# Card-Shuffler.net
KiCad netlist of a schematic drawn in Altium Designer
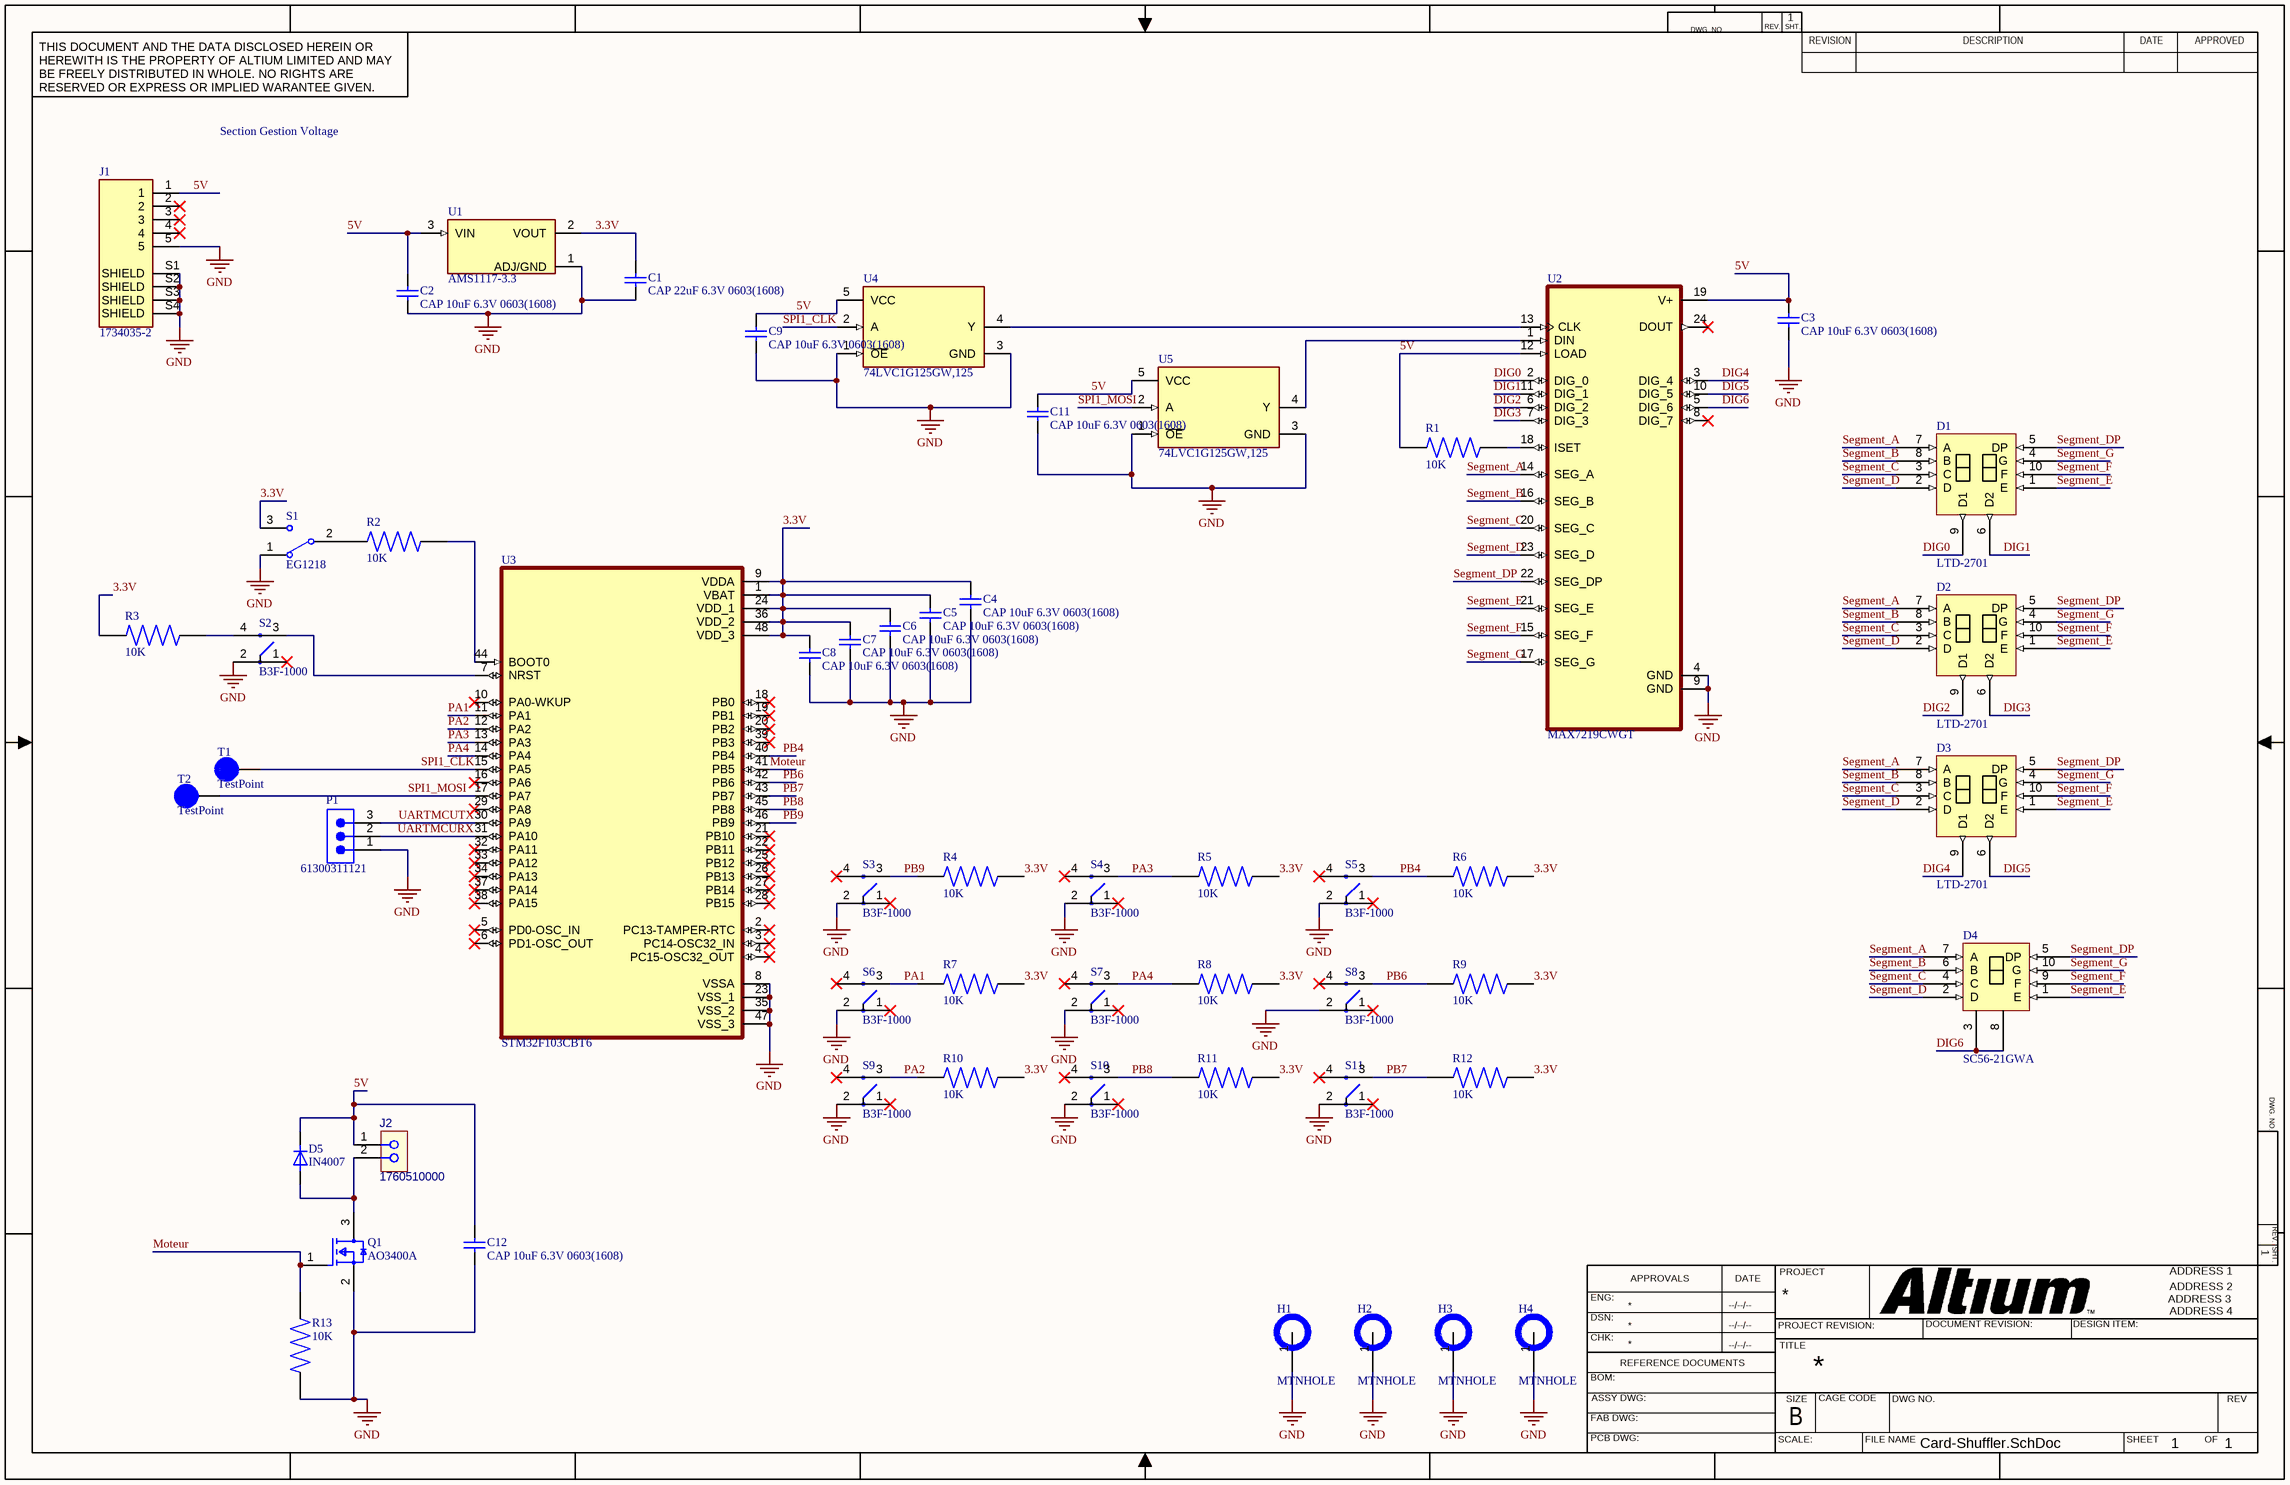
[diagram p0: Card-Shuffler.SchDoc]

(export (version "E")
  (design (tool "Eeschema 10.0.6"))
  (components
    (comp (ref "C1")
      (value "CAP 22uF 6.3V 0603(1608)")
      (footprint "CAPC0603(1608)100_M")
      (description "CAP 22uF 6.3V ±10% 0603 (1608 Metric) Thickness 1mm SMD")
      (fields (field (name "TOLERANCE") "Â±10%"))
      (libsource (lib "Altium Content Vault") (part "CAP"))
    )
    (comp (ref "C2")
      (value "CAP 10uF 6.3V 0603(1608)")
      (footprint "CAPC0603(1608)100_M")
      (description "CAP 10uF 6.3V ±10% 0603 (1608 Metric) Thickness 1mm SMD")
      (fields (field (name "TOLERANCE") "Â±10%"))
      (libsource (lib "Altium Content Vault") (part "CAP"))
    )
    (comp (ref "C3")
      (value "CAP 10uF 6.3V 0603(1608)")
      (footprint "CAPC0603(1608)100_M")
      (description "CAP 10uF 6.3V ±10% 0603 (1608 Metric) Thickness 1mm SMD")
      (fields (field (name "TOLERANCE") "Â±10%"))
      (libsource (lib "Altium Content Vault") (part "CAP"))
    )
    (comp (ref "C4")
      (value "CAP 10uF 6.3V 0603(1608)")
      (footprint "CAPC0603(1608)100_M")
      (description "CAP 10uF 6.3V ±10% 0603 (1608 Metric) Thickness 1mm SMD")
      (fields (field (name "TOLERANCE") "Â±10%"))
      (libsource (lib "Altium Content Vault") (part "CAP"))
    )
    (comp (ref "C5")
      (value "CAP 10uF 6.3V 0603(1608)")
      (footprint "CAPC0603(1608)100_M")
      (description "CAP 10uF 6.3V ±10% 0603 (1608 Metric) Thickness 1mm SMD")
      (fields (field (name "TOLERANCE") "Â±10%"))
      (libsource (lib "Altium Content Vault") (part "CAP"))
    )
    (comp (ref "C6")
      (value "CAP 10uF 6.3V 0603(1608)")
      (footprint "CAPC0603(1608)100_M")
      (description "CAP 10uF 6.3V ±10% 0603 (1608 Metric) Thickness 1mm SMD")
      (fields (field (name "TOLERANCE") "Â±10%"))
      (libsource (lib "Altium Content Vault") (part "CAP"))
    )
    (comp (ref "C7")
      (value "CAP 10uF 6.3V 0603(1608)")
      (footprint "CAPC0603(1608)100_M")
      (description "CAP 10uF 6.3V ±10% 0603 (1608 Metric) Thickness 1mm SMD")
      (fields (field (name "TOLERANCE") "Â±10%"))
      (libsource (lib "Altium Content Vault") (part "CAP"))
    )
    (comp (ref "C8")
      (value "CAP 10uF 6.3V 0603(1608)")
      (footprint "CAPC0603(1608)100_M")
      (description "CAP 10uF 6.3V ±10% 0603 (1608 Metric) Thickness 1mm SMD")
      (fields (field (name "TOLERANCE") "Â±10%"))
      (libsource (lib "Altium Content Vault") (part "CAP"))
    )
    (comp (ref "C9")
      (value "CAP 10uF 6.3V 0603(1608)")
      (footprint "CAPC0603(1608)100_M")
      (description "CAP 10uF 6.3V ±10% 0603 (1608 Metric) Thickness 1mm SMD")
      (fields (field (name "TOLERANCE") "Â±10%"))
      (libsource (lib "Altium Content Vault") (part "CAP"))
    )
    (comp (ref "C11")
      (value "CAP 10uF 6.3V 0603(1608)")
      (footprint "CAPC0603(1608)100_M")
      (description "CAP 10uF 6.3V ±10% 0603 (1608 Metric) Thickness 1mm SMD")
      (fields (field (name "TOLERANCE") "Â±10%"))
      (libsource (lib "Altium Content Vault") (part "CAP"))
    )
    (comp (ref "C12")
      (value "CAP 10uF 6.3V 0603(1608)")
      (footprint "CAPC0603(1608)100_M")
      (description "CAP 10uF 6.3V ±10% 0603 (1608 Metric) Thickness 1mm SMD")
      (fields (field (name "TOLERANCE") "Â±10%"))
      (libsource (lib "Altium Content Vault") (part "CAP"))
    )
    (comp (ref "D1")
      (value "LTD-2701")
      (footprint "LTD-701JD")
      (description "Afficheur 7-segments double")
      (libsource (lib "Pieces") (part "LTD-2701"))
    )
    (comp (ref "D2")
      (value "LTD-2701")
      (footprint "LTD-701JD")
      (description "Afficheur 7-segments double")
      (libsource (lib "Pieces") (part "LTD-2701"))
    )
    (comp (ref "D3")
      (value "LTD-2701")
      (footprint "LTD-701JD")
      (description "Afficheur 7-segments double")
      (libsource (lib "Pieces") (part "LTD-2701"))
    )
    (comp (ref "D4")
      (value "SC56-21GWA")
      (footprint "SC56-21GWA")
      (description "Afficheur 7-Segment")
      (libsource (lib "Pieces") (part "SC56-21GWA"))
    )
    (comp (ref "D5")
      (value "IN4007")
      (footprint "DIOAD1070W78L470D235P")
      (description "Diode Standard 1000 V 1A Through Hole DO-204AL (DO-41)")
      (fields (field (name "MF") "Vishay Semiconductor"))
      (libsource (lib "Pieces") (part "IN4007"))
    )
    (comp (ref "H1") (value "MTNHOLE") (footprint "MTHOLE1_LAB4") (libsource (lib "Pieces") (part "MTNHOLE")))
    (comp (ref "H2") (value "MTNHOLE") (footprint "MTHOLE1_LAB4") (libsource (lib "Pieces") (part "MTNHOLE")))
    (comp (ref "H3") (value "MTNHOLE") (footprint "MTHOLE1_LAB4") (libsource (lib "Pieces") (part "MTNHOLE")))
    (comp (ref "H4") (value "MTNHOLE") (footprint "MTHOLE1_LAB4") (libsource (lib "Pieces") (part "MTNHOLE")))
    (comp (ref "J1")
      (value "1734035-2")
      (footprint "CONN_1734035-2")
      (description "CONNECTOR, RECEPTACLE, MINI-USB, 1 PORT, SERIES B, RIGHT ANGLE ¦ TE Connectivity 1734035-2")
      (fields (field (name "MF") "TE Connectivity"))
      (libsource (lib "Pieces") (part "1734035-2"))
    )
    (comp (ref "J2")
      (value "1760510000")
      (footprint "CONN_TERM_BLOCK_2POS_5mm_Model1")
      (description "CONN TERM BLOCK 2POS 5mm pitch")
      (libsource (lib "Pieces") (part "CONN_TERM_BLOCK_2POS_5mm_MODEL2"))
    )
    (comp (ref "P1")
      (value "61300311121")
      (footprint "CONN_HDR_3POS_100MILS_TH")
      (description "Header 3pins single row, TH")
      (libsource (lib "Pieces") (part "CONN_HEADER_3POS"))
    )
    (comp (ref "Q1")
      (value "AO3400A")
      (footprint "FP-SOT23-MFG")
      (description "MOSFET N-CH 30V 5.7A SOT23")
      (libsource (lib "Altium Content Vault") (part "0a9ea7c96deaaede766a5b531c28de0"))
    )
    (comp (ref "R1")
      (value "10K")
      (footprint "RES_ERJU03F1503V")
      (description "0201 anti-sulfurated resistor 0603 Anti-Sulfurated")
      (fields (field (name "MF") "Panasonic") (field (name "MP") "ERJ-U03F1503V"))
      (libsource (lib "Pieces") (part "ERJU03F1503V"))
    )
    (comp (ref "R2")
      (value "10K")
      (footprint "RES_ERJU03F1503V")
      (description "0201 anti-sulfurated resistor 0603 Anti-Sulfurated")
      (fields (field (name "MF") "Panasonic") (field (name "MP") "ERJ-U03F1503V"))
      (libsource (lib "Pieces") (part "ERJU03F1503V"))
    )
    (comp (ref "R3")
      (value "10K")
      (footprint "RES_ERJU03F1503V")
      (description "0201 anti-sulfurated resistor 0603 Anti-Sulfurated")
      (fields (field (name "MF") "Panasonic") (field (name "MP") "ERJ-U03F1503V"))
      (libsource (lib "Pieces") (part "ERJU03F1503V"))
    )
    (comp (ref "R4")
      (value "10K")
      (footprint "RES_ERJU03F1503V")
      (description "0201 anti-sulfurated resistor 0603 Anti-Sulfurated")
      (fields (field (name "MF") "Panasonic") (field (name "MP") "ERJ-U03F1503V"))
      (libsource (lib "Pieces") (part "ERJU03F1503V"))
    )
    (comp (ref "R5")
      (value "10K")
      (footprint "RES_ERJU03F1503V")
      (description "0201 anti-sulfurated resistor 0603 Anti-Sulfurated")
      (fields (field (name "MF") "Panasonic") (field (name "MP") "ERJ-U03F1503V"))
      (libsource (lib "Pieces") (part "ERJU03F1503V"))
    )
    (comp (ref "R6")
      (value "10K")
      (footprint "RES_ERJU03F1503V")
      (description "0201 anti-sulfurated resistor 0603 Anti-Sulfurated")
      (fields (field (name "MF") "Panasonic") (field (name "MP") "ERJ-U03F1503V"))
      (libsource (lib "Pieces") (part "ERJU03F1503V"))
    )
    (comp (ref "R7")
      (value "10K")
      (footprint "RES_ERJU03F1503V")
      (description "0201 anti-sulfurated resistor 0603 Anti-Sulfurated")
      (fields (field (name "MF") "Panasonic") (field (name "MP") "ERJ-U03F1503V"))
      (libsource (lib "Pieces") (part "ERJU03F1503V"))
    )
    (comp (ref "R8")
      (value "10K")
      (footprint "RES_ERJU03F1503V")
      (description "0201 anti-sulfurated resistor 0603 Anti-Sulfurated")
      (fields (field (name "MF") "Panasonic") (field (name "MP") "ERJ-U03F1503V"))
      (libsource (lib "Pieces") (part "ERJU03F1503V"))
    )
    (comp (ref "R9")
      (value "10K")
      (footprint "RES_ERJU03F1503V")
      (description "0201 anti-sulfurated resistor 0603 Anti-Sulfurated")
      (fields (field (name "MF") "Panasonic") (field (name "MP") "ERJ-U03F1503V"))
      (libsource (lib "Pieces") (part "ERJU03F1503V"))
    )
    (comp (ref "R10")
      (value "10K")
      (footprint "RES_ERJU03F1503V")
      (description "0201 anti-sulfurated resistor 0603 Anti-Sulfurated")
      (fields (field (name "MF") "Panasonic") (field (name "MP") "ERJ-U03F1503V"))
      (libsource (lib "Pieces") (part "ERJU03F1503V"))
    )
    (comp (ref "R11")
      (value "10K")
      (footprint "RES_ERJU03F1503V")
      (description "0201 anti-sulfurated resistor 0603 Anti-Sulfurated")
      (fields (field (name "MF") "Panasonic") (field (name "MP") "ERJ-U03F1503V"))
      (libsource (lib "Pieces") (part "ERJU03F1503V"))
    )
    (comp (ref "R12")
      (value "10K")
      (footprint "RES_ERJU03F1503V")
      (description "0201 anti-sulfurated resistor 0603 Anti-Sulfurated")
      (fields (field (name "MF") "Panasonic") (field (name "MP") "ERJ-U03F1503V"))
      (libsource (lib "Pieces") (part "ERJU03F1503V"))
    )
    (comp (ref "R13")
      (value "10K")
      (footprint "RES_ERJU03F1503V")
      (description "0201 anti-sulfurated resistor 0603 Anti-Sulfurated")
      (fields (field (name "MF") "Panasonic") (field (name "MP") "ERJ-U03F1503V"))
      (libsource (lib "Pieces") (part "ERJU03F1503V"))
    )
    (comp (ref "S1")
      (value "EG1218")
      (footprint "ESWI-EG1218_V")
      (description "Slide Switch, 500 V, -20 to 70 degC, 3-Pin THD, RoHS")
      (libsource (lib "Altium Content Vault") (part "SW-SPDT-3_B"))
    )
    (comp (ref "S2")
      (value "B3F-1000")
      (footprint "SW_B3F-1000")
      (description "Switch Tactile N.O. SPST Flat Round Button PC Pins 0.05A 24VDC 1000000Cycles 0.98N Thru-Hole Bag")
      (fields (field (name "MF") "Omron") (field (name "MP") "B3F1000"))
      (libsource (lib "Pieces") (part "B3F-1000"))
    )
    (comp (ref "S3")
      (value "B3F-1000")
      (footprint "SW_B3F-1000")
      (description "Switch Tactile N.O. SPST Flat Round Button PC Pins 0.05A 24VDC 1000000Cycles 0.98N Thru-Hole Bag")
      (fields (field (name "MF") "Omron") (field (name "MP") "B3F1000"))
      (libsource (lib "Pieces") (part "B3F-1000"))
    )
    (comp (ref "S4")
      (value "B3F-1000")
      (footprint "SW_B3F-1000")
      (description "Switch Tactile N.O. SPST Flat Round Button PC Pins 0.05A 24VDC 1000000Cycles 0.98N Thru-Hole Bag")
      (fields (field (name "MF") "Omron") (field (name "MP") "B3F1000"))
      (libsource (lib "Pieces") (part "B3F-1000"))
    )
    (comp (ref "S5")
      (value "B3F-1000")
      (footprint "SW_B3F-1000")
      (description "Switch Tactile N.O. SPST Flat Round Button PC Pins 0.05A 24VDC 1000000Cycles 0.98N Thru-Hole Bag")
      (fields (field (name "MF") "Omron") (field (name "MP") "B3F1000"))
      (libsource (lib "Pieces") (part "B3F-1000"))
    )
    (comp (ref "S6")
      (value "B3F-1000")
      (footprint "SW_B3F-1000")
      (description "Switch Tactile N.O. SPST Flat Round Button PC Pins 0.05A 24VDC 1000000Cycles 0.98N Thru-Hole Bag")
      (fields (field (name "MF") "Omron") (field (name "MP") "B3F1000"))
      (libsource (lib "Pieces") (part "B3F-1000"))
    )
    (comp (ref "S7")
      (value "B3F-1000")
      (footprint "SW_B3F-1000")
      (description "Switch Tactile N.O. SPST Flat Round Button PC Pins 0.05A 24VDC 1000000Cycles 0.98N Thru-Hole Bag")
      (fields (field (name "MF") "Omron") (field (name "MP") "B3F1000"))
      (libsource (lib "Pieces") (part "B3F-1000"))
    )
    (comp (ref "S8")
      (value "B3F-1000")
      (footprint "SW_B3F-1000")
      (description "Switch Tactile N.O. SPST Flat Round Button PC Pins 0.05A 24VDC 1000000Cycles 0.98N Thru-Hole Bag")
      (fields (field (name "MF") "Omron") (field (name "MP") "B3F1000"))
      (libsource (lib "Pieces") (part "B3F-1000"))
    )
    (comp (ref "S9")
      (value "B3F-1000")
      (footprint "SW_B3F-1000")
      (description "Switch Tactile N.O. SPST Flat Round Button PC Pins 0.05A 24VDC 1000000Cycles 0.98N Thru-Hole Bag")
      (fields (field (name "MF") "Omron") (field (name "MP") "B3F1000"))
      (libsource (lib "Pieces") (part "B3F-1000"))
    )
    (comp (ref "S10")
      (value "B3F-1000")
      (footprint "SW_B3F-1000")
      (description "Switch Tactile N.O. SPST Flat Round Button PC Pins 0.05A 24VDC 1000000Cycles 0.98N Thru-Hole Bag")
      (fields (field (name "MF") "Omron") (field (name "MP") "B3F1000"))
      (libsource (lib "Pieces") (part "B3F-1000"))
    )
    (comp (ref "S11")
      (value "B3F-1000")
      (footprint "SW_B3F-1000")
      (description "Switch Tactile N.O. SPST Flat Round Button PC Pins 0.05A 24VDC 1000000Cycles 0.98N Thru-Hole Bag")
      (fields (field (name "MF") "Omron") (field (name "MP") "B3F1000"))
      (libsource (lib "Pieces") (part "B3F-1000"))
    )
    (comp (ref "T1")
      (value "TestPoint")
      (footprint "Testpoint")
      (libsource (lib "Pieces") (part "TestPoint"))
    )
    (comp (ref "T2")
      (value "TestPoint")
      (footprint "Testpoint")
      (libsource (lib "Pieces") (part "TestPoint"))
    )
    (comp (ref "U1")
      (value "AMS1117-3.3")
      (footprint "SOT229P700X180-4N")
      (description "Linear Voltage Regulator IC Positive Fixed 1 Output 1A SOT-223-3L")
      (fields (field (name "MF") "UMW"))
      (libsource (lib "Pieces") (part "AMS1117-3.3"))
    )
    (comp (ref "U2")
      (value "MAX7219CWGT")
      (footprint "SOIC127P1032X265-24N")
      (description "IC DRVR 7 SEGMNT 8 DIGIT 24SOIC")
      (fields (field (name "MF") "Analog Devices") (field (name "MP") "MAX7219CWG+"))
      (libsource (lib "Pieces") (part "MAX7219CWGT"))
    )
    (comp (ref "U3")
      (value "STM32F103CBT6")
      (footprint "QFP50P900X900X160-48N")
      (description "ARMÂ® CortexÂ®-M3 STM32F1 Microcontroller IC 32-Bit Single-Core 72MHz 128KB (128K x 8) FLASH")
      (fields (field (name "MF") "STMicroelectronics"))
      (libsource (lib "Pieces") (part "STM32F103CBT6"))
    )
    (comp (ref "U4")
      (value "74LVC1G125GW,125")
      (footprint "FP-SOT353-1-IPC_A")
      (description "IC BUF NON-INVERT 5.5V 5TSSOP")
      (libsource (lib "Altium Content Vault") (part "ce4f934f0121cbd2948622023bc44d6"))
    )
    (comp (ref "U5")
      (value "74LVC1G125GW,125")
      (footprint "FP-SOT353-1-IPC_A")
      (description "IC BUF NON-INVERT 5.5V 5TSSOP")
      (libsource (lib "Altium Content Vault") (part "ce4f934f0121cbd2948622023bc44d6"))
    )
  )
  (nets
    (net (code "1") (name "/3.3V") (class "Default")
      (node (ref "C1") (pin "2") (pinfunction "2_2") (pintype "passive"))
      (node (ref "C4") (pin "2") (pinfunction "2_2") (pintype "passive"))
      (node (ref "C5") (pin "2") (pinfunction "2_2") (pintype "passive"))
      (node (ref "C6") (pin "2") (pinfunction "2_2") (pintype "passive"))
      (node (ref "C7") (pin "2") (pinfunction "2_2") (pintype "passive"))
      (node (ref "C8") (pin "2") (pinfunction "2_2") (pintype "passive"))
      (node (ref "R10") (pin "2") (pinfunction "2_2") (pintype "passive"))
      (node (ref "R11") (pin "2") (pinfunction "2_2") (pintype "passive"))
      (node (ref "R12") (pin "2") (pinfunction "2_2") (pintype "passive"))
      (node (ref "R3") (pin "1") (pinfunction "1_1") (pintype "passive"))
      (node (ref "R4") (pin "2") (pinfunction "2_2") (pintype "passive"))
      (node (ref "R5") (pin "2") (pinfunction "2_2") (pintype "passive"))
      (node (ref "R6") (pin "2") (pinfunction "2_2") (pintype "passive"))
      (node (ref "R7") (pin "2") (pinfunction "2_2") (pintype "passive"))
      (node (ref "R8") (pin "2") (pinfunction "2_2") (pintype "passive"))
      (node (ref "R9") (pin "2") (pinfunction "2_2") (pintype "passive"))
      (node (ref "S1") (pin "3") (pinfunction "3_3") (pintype "passive"))
      (node (ref "U1") (pin "2") (pinfunction "VOUT_2") (pintype "passive"))
      (node (ref "U3") (pin "1") (pinfunction "VBAT_1") (pintype "power_in"))
      (node (ref "U3") (pin "24") (pinfunction "VDD_1_24") (pintype "power_in"))
      (node (ref "U3") (pin "36") (pinfunction "VDD_2_36") (pintype "power_in"))
      (node (ref "U3") (pin "48") (pinfunction "VDD_3_48") (pintype "power_in"))
      (node (ref "U3") (pin "9") (pinfunction "VDDA_9") (pintype "power_in"))
    )
    (net (code "2") (name "/5V") (class "Default")
      (node (ref "C11") (pin "2") (pinfunction "2_2") (pintype "passive"))
      (node (ref "C12") (pin "2") (pinfunction "2_2") (pintype "passive"))
      (node (ref "C2") (pin "2") (pinfunction "2_2") (pintype "passive"))
      (node (ref "C3") (pin "2") (pinfunction "2_2") (pintype "passive"))
      (node (ref "C9") (pin "1") (pinfunction "1_1") (pintype "passive"))
      (node (ref "D5") (pin "C") (pinfunction "C_C") (pintype "passive"))
      (node (ref "J1") (pin "1") (pinfunction "1_1") (pintype "passive"))
      (node (ref "J2") (pin "1") (pinfunction "1_1") (pintype "passive"))
      (node (ref "R1") (pin "1") (pinfunction "1_1") (pintype "passive"))
      (node (ref "U1") (pin "3") (pinfunction "VIN_3") (pintype "input"))
      (node (ref "U2") (pin "12") (pinfunction "LOAD_12") (pintype "input"))
      (node (ref "U2") (pin "19") (pinfunction "V+_19") (pintype "power_in"))
      (node (ref "U4") (pin "5") (pinfunction "VCC_5") (pintype "power_in"))
      (node (ref "U5") (pin "5") (pinfunction "VCC_5") (pintype "power_in"))
    )
    (net (code "3") (name "/DIG0") (class "Default")
      (node (ref "D1") (pin "9") (pinfunction "D1_9") (pintype "output"))
      (node (ref "U2") (pin "2") (pinfunction "DIG_0_2") (pintype "bidirectional"))
    )
    (net (code "4") (name "/DIG1") (class "Default")
      (node (ref "D1") (pin "6") (pinfunction "D2_6") (pintype "output"))
      (node (ref "U2") (pin "11") (pinfunction "DIG_1_11") (pintype "bidirectional"))
    )
    (net (code "5") (name "/DIG2") (class "Default")
      (node (ref "D2") (pin "9") (pinfunction "D1_9") (pintype "output"))
      (node (ref "U2") (pin "6") (pinfunction "DIG_2_6") (pintype "bidirectional"))
    )
    (net (code "6") (name "/DIG3") (class "Default")
      (node (ref "D2") (pin "6") (pinfunction "D2_6") (pintype "output"))
      (node (ref "U2") (pin "7") (pinfunction "DIG_3_7") (pintype "bidirectional"))
    )
    (net (code "7") (name "/DIG4") (class "Default")
      (node (ref "D3") (pin "9") (pinfunction "D1_9") (pintype "output"))
      (node (ref "U2") (pin "3") (pinfunction "DIG_4_3") (pintype "bidirectional"))
    )
    (net (code "8") (name "/DIG5") (class "Default")
      (node (ref "D3") (pin "6") (pinfunction "D2_6") (pintype "output"))
      (node (ref "U2") (pin "10") (pinfunction "DIG_5_10") (pintype "bidirectional"))
    )
    (net (code "9") (name "/DIG6") (class "Default")
      (node (ref "D4") (pin "3") (pintype "power_in"))
      (node (ref "D4") (pin "8") (pintype "power_in"))
      (node (ref "U2") (pin "5") (pinfunction "DIG_6_5") (pintype "bidirectional"))
    )
    (net (code "10") (name "/Moteur") (class "Default")
      (node (ref "Q1") (pin "1") (pinfunction "G_1") (pintype "passive"))
      (node (ref "R13") (pin "2") (pinfunction "2_2") (pintype "passive"))
      (node (ref "U3") (pin "41") (pinfunction "PB5_41") (pintype "bidirectional"))
    )
    (net (code "11") (name "/PA1") (class "Default")
      (node (ref "R7") (pin "1") (pinfunction "1_1") (pintype "passive"))
      (node (ref "S6") (pin "3") (pinfunction "3_3") (pintype "passive"))
      (node (ref "U3") (pin "11") (pinfunction "PA1_11") (pintype "bidirectional"))
    )
    (net (code "12") (name "/PA2") (class "Default")
      (node (ref "R10") (pin "1") (pinfunction "1_1") (pintype "passive"))
      (node (ref "S9") (pin "3") (pinfunction "3_3") (pintype "passive"))
      (node (ref "U3") (pin "12") (pinfunction "PA2_12") (pintype "bidirectional"))
    )
    (net (code "13") (name "/PA3") (class "Default")
      (node (ref "R5") (pin "1") (pinfunction "1_1") (pintype "passive"))
      (node (ref "S4") (pin "3") (pinfunction "3_3") (pintype "passive"))
      (node (ref "U3") (pin "13") (pinfunction "PA3_13") (pintype "bidirectional"))
    )
    (net (code "14") (name "/PA4") (class "Default")
      (node (ref "R8") (pin "1") (pinfunction "1_1") (pintype "passive"))
      (node (ref "S7") (pin "3") (pinfunction "3_3") (pintype "passive"))
      (node (ref "U3") (pin "14") (pinfunction "PA4_14") (pintype "bidirectional"))
    )
    (net (code "15") (name "/PB4") (class "Default")
      (node (ref "R6") (pin "1") (pinfunction "1_1") (pintype "passive"))
      (node (ref "S5") (pin "3") (pinfunction "3_3") (pintype "passive"))
      (node (ref "U3") (pin "40") (pinfunction "PB4_40") (pintype "bidirectional"))
    )
    (net (code "16") (name "/PB6") (class "Default")
      (node (ref "R9") (pin "1") (pinfunction "1_1") (pintype "passive"))
      (node (ref "S8") (pin "3") (pinfunction "3_3") (pintype "passive"))
      (node (ref "U3") (pin "42") (pinfunction "PB6_42") (pintype "bidirectional"))
    )
    (net (code "17") (name "/PB7") (class "Default")
      (node (ref "R12") (pin "1") (pinfunction "1_1") (pintype "passive"))
      (node (ref "S11") (pin "3") (pinfunction "3_3") (pintype "passive"))
      (node (ref "U3") (pin "43") (pinfunction "PB7_43") (pintype "bidirectional"))
    )
    (net (code "18") (name "/PB8") (class "Default")
      (node (ref "R11") (pin "1") (pinfunction "1_1") (pintype "passive"))
      (node (ref "S10") (pin "3") (pinfunction "3_3") (pintype "passive"))
      (node (ref "U3") (pin "45") (pinfunction "PB8_45") (pintype "bidirectional"))
    )
    (net (code "19") (name "/PB9") (class "Default")
      (node (ref "R4") (pin "1") (pinfunction "1_1") (pintype "passive"))
      (node (ref "S3") (pin "3") (pinfunction "3_3") (pintype "passive"))
      (node (ref "U3") (pin "46") (pinfunction "PB9_46") (pintype "bidirectional"))
    )
    (net (code "20") (name "/SPI1_CLK") (class "Default")
      (node (ref "T1") (pin "1") (pinfunction "1_1") (pintype "passive"))
      (node (ref "U3") (pin "15") (pinfunction "PA5_15") (pintype "bidirectional"))
      (node (ref "U4") (pin "2") (pinfunction "A_2") (pintype "input"))
    )
    (net (code "21") (name "/SPI1_MOSI") (class "Default")
      (node (ref "T2") (pin "1") (pinfunction "1_1") (pintype "passive"))
      (node (ref "U3") (pin "17") (pinfunction "PA7_17") (pintype "bidirectional"))
      (node (ref "U5") (pin "2") (pinfunction "A_2") (pintype "input"))
    )
    (net (code "22") (name "/Segment_A") (class "Default")
      (node (ref "D1") (pin "7") (pinfunction "A_7") (pintype "input"))
      (node (ref "D2") (pin "7") (pinfunction "A_7") (pintype "input"))
      (node (ref "D3") (pin "7") (pinfunction "A_7") (pintype "input"))
      (node (ref "D4") (pin "7") (pinfunction "A_7") (pintype "input"))
      (node (ref "U2") (pin "14") (pinfunction "SEG_A_14") (pintype "bidirectional"))
    )
    (net (code "23") (name "/Segment_B") (class "Default")
      (node (ref "D1") (pin "8") (pinfunction "B_8") (pintype "input"))
      (node (ref "D2") (pin "8") (pinfunction "B_8") (pintype "input"))
      (node (ref "D3") (pin "8") (pinfunction "B_8") (pintype "input"))
      (node (ref "D4") (pin "6") (pinfunction "B_6") (pintype "input"))
      (node (ref "U2") (pin "16") (pinfunction "SEG_B_16") (pintype "bidirectional"))
    )
    (net (code "24") (name "/Segment_C") (class "Default")
      (node (ref "D1") (pin "3") (pinfunction "C_3") (pintype "input"))
      (node (ref "D2") (pin "3") (pinfunction "C_3") (pintype "input"))
      (node (ref "D3") (pin "3") (pinfunction "C_3") (pintype "input"))
      (node (ref "D4") (pin "4") (pinfunction "C_4") (pintype "input"))
      (node (ref "U2") (pin "20") (pinfunction "SEG_C_20") (pintype "bidirectional"))
    )
    (net (code "25") (name "/Segment_D") (class "Default")
      (node (ref "D1") (pin "2") (pinfunction "D_2") (pintype "input"))
      (node (ref "D2") (pin "2") (pinfunction "D_2") (pintype "input"))
      (node (ref "D3") (pin "2") (pinfunction "D_2") (pintype "input"))
      (node (ref "D4") (pin "2") (pinfunction "D_2") (pintype "input"))
      (node (ref "U2") (pin "23") (pinfunction "SEG_D_23") (pintype "bidirectional"))
    )
    (net (code "26") (name "/Segment_DP") (class "Default")
      (node (ref "D1") (pin "5") (pinfunction "DP_5") (pintype "input"))
      (node (ref "D2") (pin "5") (pinfunction "DP_5") (pintype "input"))
      (node (ref "D3") (pin "5") (pinfunction "DP_5") (pintype "input"))
      (node (ref "D4") (pin "5") (pinfunction "DP_5") (pintype "input"))
      (node (ref "U2") (pin "22") (pinfunction "SEG_DP_22") (pintype "bidirectional"))
    )
    (net (code "27") (name "/Segment_E") (class "Default")
      (node (ref "D1") (pin "1") (pinfunction "E_1") (pintype "input"))
      (node (ref "D2") (pin "1") (pinfunction "E_1") (pintype "input"))
      (node (ref "D3") (pin "1") (pinfunction "E_1") (pintype "input"))
      (node (ref "D4") (pin "1") (pinfunction "E_1") (pintype "input"))
      (node (ref "U2") (pin "21") (pinfunction "SEG_E_21") (pintype "bidirectional"))
    )
    (net (code "28") (name "/Segment_F") (class "Default")
      (node (ref "D1") (pin "10") (pinfunction "F_10") (pintype "input"))
      (node (ref "D2") (pin "10") (pinfunction "F_10") (pintype "input"))
      (node (ref "D3") (pin "10") (pinfunction "F_10") (pintype "input"))
      (node (ref "D4") (pin "9") (pinfunction "F_9") (pintype "input"))
      (node (ref "U2") (pin "15") (pinfunction "SEG_F_15") (pintype "bidirectional"))
    )
    (net (code "29") (name "/Segment_G") (class "Default")
      (node (ref "D1") (pin "4") (pinfunction "G_4") (pintype "input"))
      (node (ref "D2") (pin "4") (pinfunction "G_4") (pintype "input"))
      (node (ref "D3") (pin "4") (pinfunction "G_4") (pintype "input"))
      (node (ref "D4") (pin "10") (pinfunction "G_10") (pintype "input"))
      (node (ref "U2") (pin "17") (pinfunction "SEG_G_17") (pintype "bidirectional"))
    )
    (net (code "30") (name "/UARTMCURX") (class "Default")
      (node (ref "P1") (pin "2") (pinfunction "2_2") (pintype "passive"))
      (node (ref "U3") (pin "31") (pinfunction "PA10_31") (pintype "bidirectional"))
    )
    (net (code "31") (name "/UARTMCUTX") (class "Default")
      (node (ref "P1") (pin "3") (pinfunction "3_3") (pintype "passive"))
      (node (ref "U3") (pin "30") (pinfunction "PA9_30") (pintype "bidirectional"))
    )
    (net (code "32") (name "GND") (class "Default")
      (node (ref "C1") (pin "1") (pinfunction "1_1") (pintype "passive"))
      (node (ref "C11") (pin "1") (pinfunction "1_1") (pintype "passive"))
      (node (ref "C12") (pin "1") (pinfunction "1_1") (pintype "passive"))
      (node (ref "C2") (pin "1") (pinfunction "1_1") (pintype "passive"))
      (node (ref "C3") (pin "1") (pinfunction "1_1") (pintype "passive"))
      (node (ref "C4") (pin "1") (pinfunction "1_1") (pintype "passive"))
      (node (ref "C5") (pin "1") (pinfunction "1_1") (pintype "passive"))
      (node (ref "C6") (pin "1") (pinfunction "1_1") (pintype "passive"))
      (node (ref "C7") (pin "1") (pinfunction "1_1") (pintype "passive"))
      (node (ref "C8") (pin "1") (pinfunction "1_1") (pintype "passive"))
      (node (ref "C9") (pin "2") (pinfunction "2_2") (pintype "passive"))
      (node (ref "H1") (pin "1") (pintype "passive"))
      (node (ref "H2") (pin "1") (pintype "passive"))
      (node (ref "H3") (pin "1") (pintype "passive"))
      (node (ref "H4") (pin "1") (pintype "passive"))
      (node (ref "J1") (pin "5") (pinfunction "5_5") (pintype "passive"))
      (node (ref "J1") (pin "S1") (pinfunction "SHIELD_S1") (pintype "passive"))
      (node (ref "J1") (pin "S2") (pinfunction "SHIELD_S2") (pintype "passive"))
      (node (ref "J1") (pin "S3") (pinfunction "SHIELD_S3") (pintype "passive"))
      (node (ref "J1") (pin "S4") (pinfunction "SHIELD_S4") (pintype "passive"))
      (node (ref "P1") (pin "1") (pinfunction "1_1") (pintype "passive"))
      (node (ref "Q1") (pin "2") (pinfunction "S_2") (pintype "passive"))
      (node (ref "R13") (pin "1") (pinfunction "1_1") (pintype "passive"))
      (node (ref "S1") (pin "1") (pinfunction "1_1") (pintype "passive"))
      (node (ref "S10") (pin "2") (pinfunction "2_2") (pintype "passive"))
      (node (ref "S11") (pin "2") (pinfunction "2_2") (pintype "passive"))
      (node (ref "S2") (pin "2") (pinfunction "2_2") (pintype "passive"))
      (node (ref "S3") (pin "2") (pinfunction "2_2") (pintype "passive"))
      (node (ref "S4") (pin "2") (pinfunction "2_2") (pintype "passive"))
      (node (ref "S5") (pin "2") (pinfunction "2_2") (pintype "passive"))
      (node (ref "S6") (pin "2") (pinfunction "2_2") (pintype "passive"))
      (node (ref "S7") (pin "2") (pinfunction "2_2") (pintype "passive"))
      (node (ref "S8") (pin "2") (pinfunction "2_2") (pintype "passive"))
      (node (ref "S9") (pin "2") (pinfunction "2_2") (pintype "passive"))
      (node (ref "U1") (pin "1") (pinfunction "ADJ/GND_1") (pintype "power_in"))
      (node (ref "U2") (pin "4") (pinfunction "GND_4") (pintype "power_in"))
      (node (ref "U2") (pin "9") (pinfunction "GND_9") (pintype "power_in"))
      (node (ref "U3") (pin "23") (pinfunction "VSS_1_23") (pintype "power_in"))
      (node (ref "U3") (pin "35") (pinfunction "VSS_2_35") (pintype "power_in"))
      (node (ref "U3") (pin "47") (pinfunction "VSS_3_47") (pintype "power_in"))
      (node (ref "U3") (pin "8") (pinfunction "VSSA_8") (pintype "power_in"))
      (node (ref "U4") (pin "1") (pinfunction "~{OE}_1") (pintype "input"))
      (node (ref "U4") (pin "3") (pinfunction "GND_3") (pintype "power_in"))
      (node (ref "U5") (pin "1") (pinfunction "~{OE}_1") (pintype "input"))
      (node (ref "U5") (pin "3") (pinfunction "GND_3") (pintype "power_in"))
    )
    (net (code "33") (name "Net-(Q1-D)") (class "Default")
      (node (ref "D5") (pin "A") (pinfunction "A_A") (pintype "passive"))
      (node (ref "J2") (pin "2") (pinfunction "2_2") (pintype "passive"))
      (node (ref "Q1") (pin "3") (pinfunction "D_3") (pintype "passive"))
    )
    (net (code "34") (name "Net-(R3-Pad2)") (class "Default")
      (node (ref "R3") (pin "2") (pinfunction "2_2") (pintype "passive"))
      (node (ref "S2") (pin "4") (pinfunction "4_4") (pintype "passive"))
    )
    (net (code "35") (name "Net-(S1-COM)") (class "Default")
      (node (ref "R2") (pin "1") (pinfunction "1_1") (pintype "passive"))
      (node (ref "S1") (pin "2") (pinfunction "COM_2") (pintype "passive"))
    )
    (net (code "36") (name "Net-(U2-CLK)") (class "Default")
      (node (ref "U2") (pin "13") (pinfunction "CLK_13") (pintype "input"))
      (node (ref "U4") (pin "4") (pinfunction "Y_4") (pintype "tri_state"))
    )
    (net (code "37") (name "Net-(U2-DIN)") (class "Default")
      (node (ref "U2") (pin "1") (pinfunction "DIN_1") (pintype "input"))
      (node (ref "U5") (pin "4") (pinfunction "Y_4") (pintype "tri_state"))
    )
    (net (code "38") (name "Net-(U2-ISET)") (class "Default")
      (node (ref "R1") (pin "2") (pinfunction "2_2") (pintype "passive"))
      (node (ref "U2") (pin "18") (pinfunction "ISET_18") (pintype "bidirectional"))
    )
    (net (code "39") (name "Net-(U3-BOOT0)") (class "Default")
      (node (ref "R2") (pin "2") (pinfunction "2_2") (pintype "passive"))
      (node (ref "U3") (pin "44") (pinfunction "BOOT0_44") (pintype "input"))
    )
    (net (code "40") (name "Net-(U3-NRST)") (class "Default")
      (node (ref "S2") (pin "3") (pinfunction "3_3") (pintype "passive"))
      (node (ref "U3") (pin "7") (pinfunction "NRST_7") (pintype "bidirectional"))
    )
    (net (code "41") (name "unconnected-(J1-Pad2)") (class "Default")
      (node (ref "J1") (pin "2") (pinfunction "2_2") (pintype "passive+no_connect"))
    )
    (net (code "42") (name "unconnected-(J1-Pad3)") (class "Default")
      (node (ref "J1") (pin "3") (pinfunction "3_3") (pintype "passive+no_connect"))
    )
    (net (code "43") (name "unconnected-(J1-Pad4)") (class "Default")
      (node (ref "J1") (pin "4") (pinfunction "4_4") (pintype "passive+no_connect"))
    )
    (net (code "44") (name "unconnected-(S2-Pad1)") (class "Default")
      (node (ref "S2") (pin "1") (pinfunction "1_1") (pintype "passive+no_connect"))
    )
    (net (code "45") (name "unconnected-(S3-Pad1)") (class "Default")
      (node (ref "S3") (pin "1") (pinfunction "1_1") (pintype "passive+no_connect"))
    )
    (net (code "46") (name "unconnected-(S3-Pad4)") (class "Default")
      (node (ref "S3") (pin "4") (pinfunction "4_4") (pintype "passive+no_connect"))
    )
    (net (code "47") (name "unconnected-(S4-Pad1)") (class "Default")
      (node (ref "S4") (pin "1") (pinfunction "1_1") (pintype "passive+no_connect"))
    )
    (net (code "48") (name "unconnected-(S4-Pad4)") (class "Default")
      (node (ref "S4") (pin "4") (pinfunction "4_4") (pintype "passive+no_connect"))
    )
    (net (code "49") (name "unconnected-(S5-Pad1)") (class "Default")
      (node (ref "S5") (pin "1") (pinfunction "1_1") (pintype "passive+no_connect"))
    )
    (net (code "50") (name "unconnected-(S5-Pad4)") (class "Default")
      (node (ref "S5") (pin "4") (pinfunction "4_4") (pintype "passive+no_connect"))
    )
    (net (code "51") (name "unconnected-(S6-Pad1)") (class "Default")
      (node (ref "S6") (pin "1") (pinfunction "1_1") (pintype "passive+no_connect"))
    )
    (net (code "52") (name "unconnected-(S6-Pad4)") (class "Default")
      (node (ref "S6") (pin "4") (pinfunction "4_4") (pintype "passive+no_connect"))
    )
    (net (code "53") (name "unconnected-(S7-Pad1)") (class "Default")
      (node (ref "S7") (pin "1") (pinfunction "1_1") (pintype "passive+no_connect"))
    )
    (net (code "54") (name "unconnected-(S7-Pad4)") (class "Default")
      (node (ref "S7") (pin "4") (pinfunction "4_4") (pintype "passive+no_connect"))
    )
    (net (code "55") (name "unconnected-(S8-Pad1)") (class "Default")
      (node (ref "S8") (pin "1") (pinfunction "1_1") (pintype "passive+no_connect"))
    )
    (net (code "56") (name "unconnected-(S8-Pad4)") (class "Default")
      (node (ref "S8") (pin "4") (pinfunction "4_4") (pintype "passive+no_connect"))
    )
    (net (code "57") (name "unconnected-(S9-Pad1)") (class "Default")
      (node (ref "S9") (pin "1") (pinfunction "1_1") (pintype "passive+no_connect"))
    )
    (net (code "58") (name "unconnected-(S9-Pad4)") (class "Default")
      (node (ref "S9") (pin "4") (pinfunction "4_4") (pintype "passive+no_connect"))
    )
    (net (code "59") (name "unconnected-(S10-Pad1)") (class "Default")
      (node (ref "S10") (pin "1") (pinfunction "1_1") (pintype "passive+no_connect"))
    )
    (net (code "60") (name "unconnected-(S10-Pad4)") (class "Default")
      (node (ref "S10") (pin "4") (pinfunction "4_4") (pintype "passive+no_connect"))
    )
    (net (code "61") (name "unconnected-(S11-Pad1)") (class "Default")
      (node (ref "S11") (pin "1") (pinfunction "1_1") (pintype "passive+no_connect"))
    )
    (net (code "62") (name "unconnected-(S11-Pad4)") (class "Default")
      (node (ref "S11") (pin "4") (pinfunction "4_4") (pintype "passive+no_connect"))
    )
    (net (code "63") (name "unconnected-(U2-DIG_7-Pad8)") (class "Default")
      (node (ref "U2") (pin "8") (pinfunction "DIG_7_8") (pintype "bidirectional+no_connect"))
    )
    (net (code "64") (name "unconnected-(U2-DOUT-Pad24)") (class "Default")
      (node (ref "U2") (pin "24") (pinfunction "DOUT_24") (pintype "output+no_connect"))
    )
    (net (code "65") (name "unconnected-(U3-PA0-WKUP-Pad10)") (class "Default")
      (node (ref "U3") (pin "10") (pinfunction "PA0-WKUP_10") (pintype "bidirectional+no_connect"))
    )
    (net (code "66") (name "unconnected-(U3-PA6-Pad16)") (class "Default")
      (node (ref "U3") (pin "16") (pinfunction "PA6_16") (pintype "bidirectional+no_connect"))
    )
    (net (code "67") (name "unconnected-(U3-PA8-Pad29)") (class "Default")
      (node (ref "U3") (pin "29") (pinfunction "PA8_29") (pintype "bidirectional+no_connect"))
    )
    (net (code "68") (name "unconnected-(U3-PA11-Pad32)") (class "Default")
      (node (ref "U3") (pin "32") (pinfunction "PA11_32") (pintype "bidirectional+no_connect"))
    )
    (net (code "69") (name "unconnected-(U3-PA12-Pad33)") (class "Default")
      (node (ref "U3") (pin "33") (pinfunction "PA12_33") (pintype "bidirectional+no_connect"))
    )
    (net (code "70") (name "unconnected-(U3-PA13-Pad34)") (class "Default")
      (node (ref "U3") (pin "34") (pinfunction "PA13_34") (pintype "bidirectional+no_connect"))
    )
    (net (code "71") (name "unconnected-(U3-PA14-Pad37)") (class "Default")
      (node (ref "U3") (pin "37") (pinfunction "PA14_37") (pintype "bidirectional+no_connect"))
    )
    (net (code "72") (name "unconnected-(U3-PA15-Pad38)") (class "Default")
      (node (ref "U3") (pin "38") (pinfunction "PA15_38") (pintype "bidirectional+no_connect"))
    )
    (net (code "73") (name "unconnected-(U3-PB0-Pad18)") (class "Default")
      (node (ref "U3") (pin "18") (pinfunction "PB0_18") (pintype "bidirectional+no_connect"))
    )
    (net (code "74") (name "unconnected-(U3-PB1-Pad19)") (class "Default")
      (node (ref "U3") (pin "19") (pinfunction "PB1_19") (pintype "bidirectional+no_connect"))
    )
    (net (code "75") (name "unconnected-(U3-PB2-Pad20)") (class "Default")
      (node (ref "U3") (pin "20") (pinfunction "PB2_20") (pintype "bidirectional+no_connect"))
    )
    (net (code "76") (name "unconnected-(U3-PB3-Pad39)") (class "Default")
      (node (ref "U3") (pin "39") (pinfunction "PB3_39") (pintype "bidirectional+no_connect"))
    )
    (net (code "77") (name "unconnected-(U3-PB10-Pad21)") (class "Default")
      (node (ref "U3") (pin "21") (pinfunction "PB10_21") (pintype "bidirectional+no_connect"))
    )
    (net (code "78") (name "unconnected-(U3-PB11-Pad22)") (class "Default")
      (node (ref "U3") (pin "22") (pinfunction "PB11_22") (pintype "bidirectional+no_connect"))
    )
    (net (code "79") (name "unconnected-(U3-PB12-Pad25)") (class "Default")
      (node (ref "U3") (pin "25") (pinfunction "PB12_25") (pintype "bidirectional+no_connect"))
    )
    (net (code "80") (name "unconnected-(U3-PB13-Pad26)") (class "Default")
      (node (ref "U3") (pin "26") (pinfunction "PB13_26") (pintype "bidirectional+no_connect"))
    )
    (net (code "81") (name "unconnected-(U3-PB14-Pad27)") (class "Default")
      (node (ref "U3") (pin "27") (pinfunction "PB14_27") (pintype "bidirectional+no_connect"))
    )
    (net (code "82") (name "unconnected-(U3-PB15-Pad28)") (class "Default")
      (node (ref "U3") (pin "28") (pinfunction "PB15_28") (pintype "bidirectional+no_connect"))
    )
    (net (code "83") (name "unconnected-(U3-PC13-TAMPER-RTC-Pad2)") (class "Default")
      (node (ref "U3") (pin "2") (pinfunction "PC13-TAMPER-RTC_2") (pintype "bidirectional+no_connect"))
    )
    (net (code "84") (name "unconnected-(U3-PC14-OSC32_IN-Pad3)") (class "Default")
      (node (ref "U3") (pin "3") (pinfunction "PC14-OSC32_IN_3") (pintype "bidirectional+no_connect"))
    )
    (net (code "85") (name "unconnected-(U3-PC15-OSC32_OUT-Pad4)") (class "Default")
      (node (ref "U3") (pin "4") (pinfunction "PC15-OSC32_OUT_4") (pintype "bidirectional+no_connect"))
    )
    (net (code "86") (name "unconnected-(U3-PD0-OSC_IN-Pad5)") (class "Default")
      (node (ref "U3") (pin "5") (pinfunction "PD0-OSC_IN_5") (pintype "bidirectional+no_connect"))
    )
    (net (code "87") (name "unconnected-(U3-PD1-OSC_OUT-Pad6)") (class "Default")
      (node (ref "U3") (pin "6") (pinfunction "PD1-OSC_OUT_6") (pintype "bidirectional+no_connect"))
    )
  )
)
